# Intercom.net
KiCad netlist of a schematic drawn in EAGLE
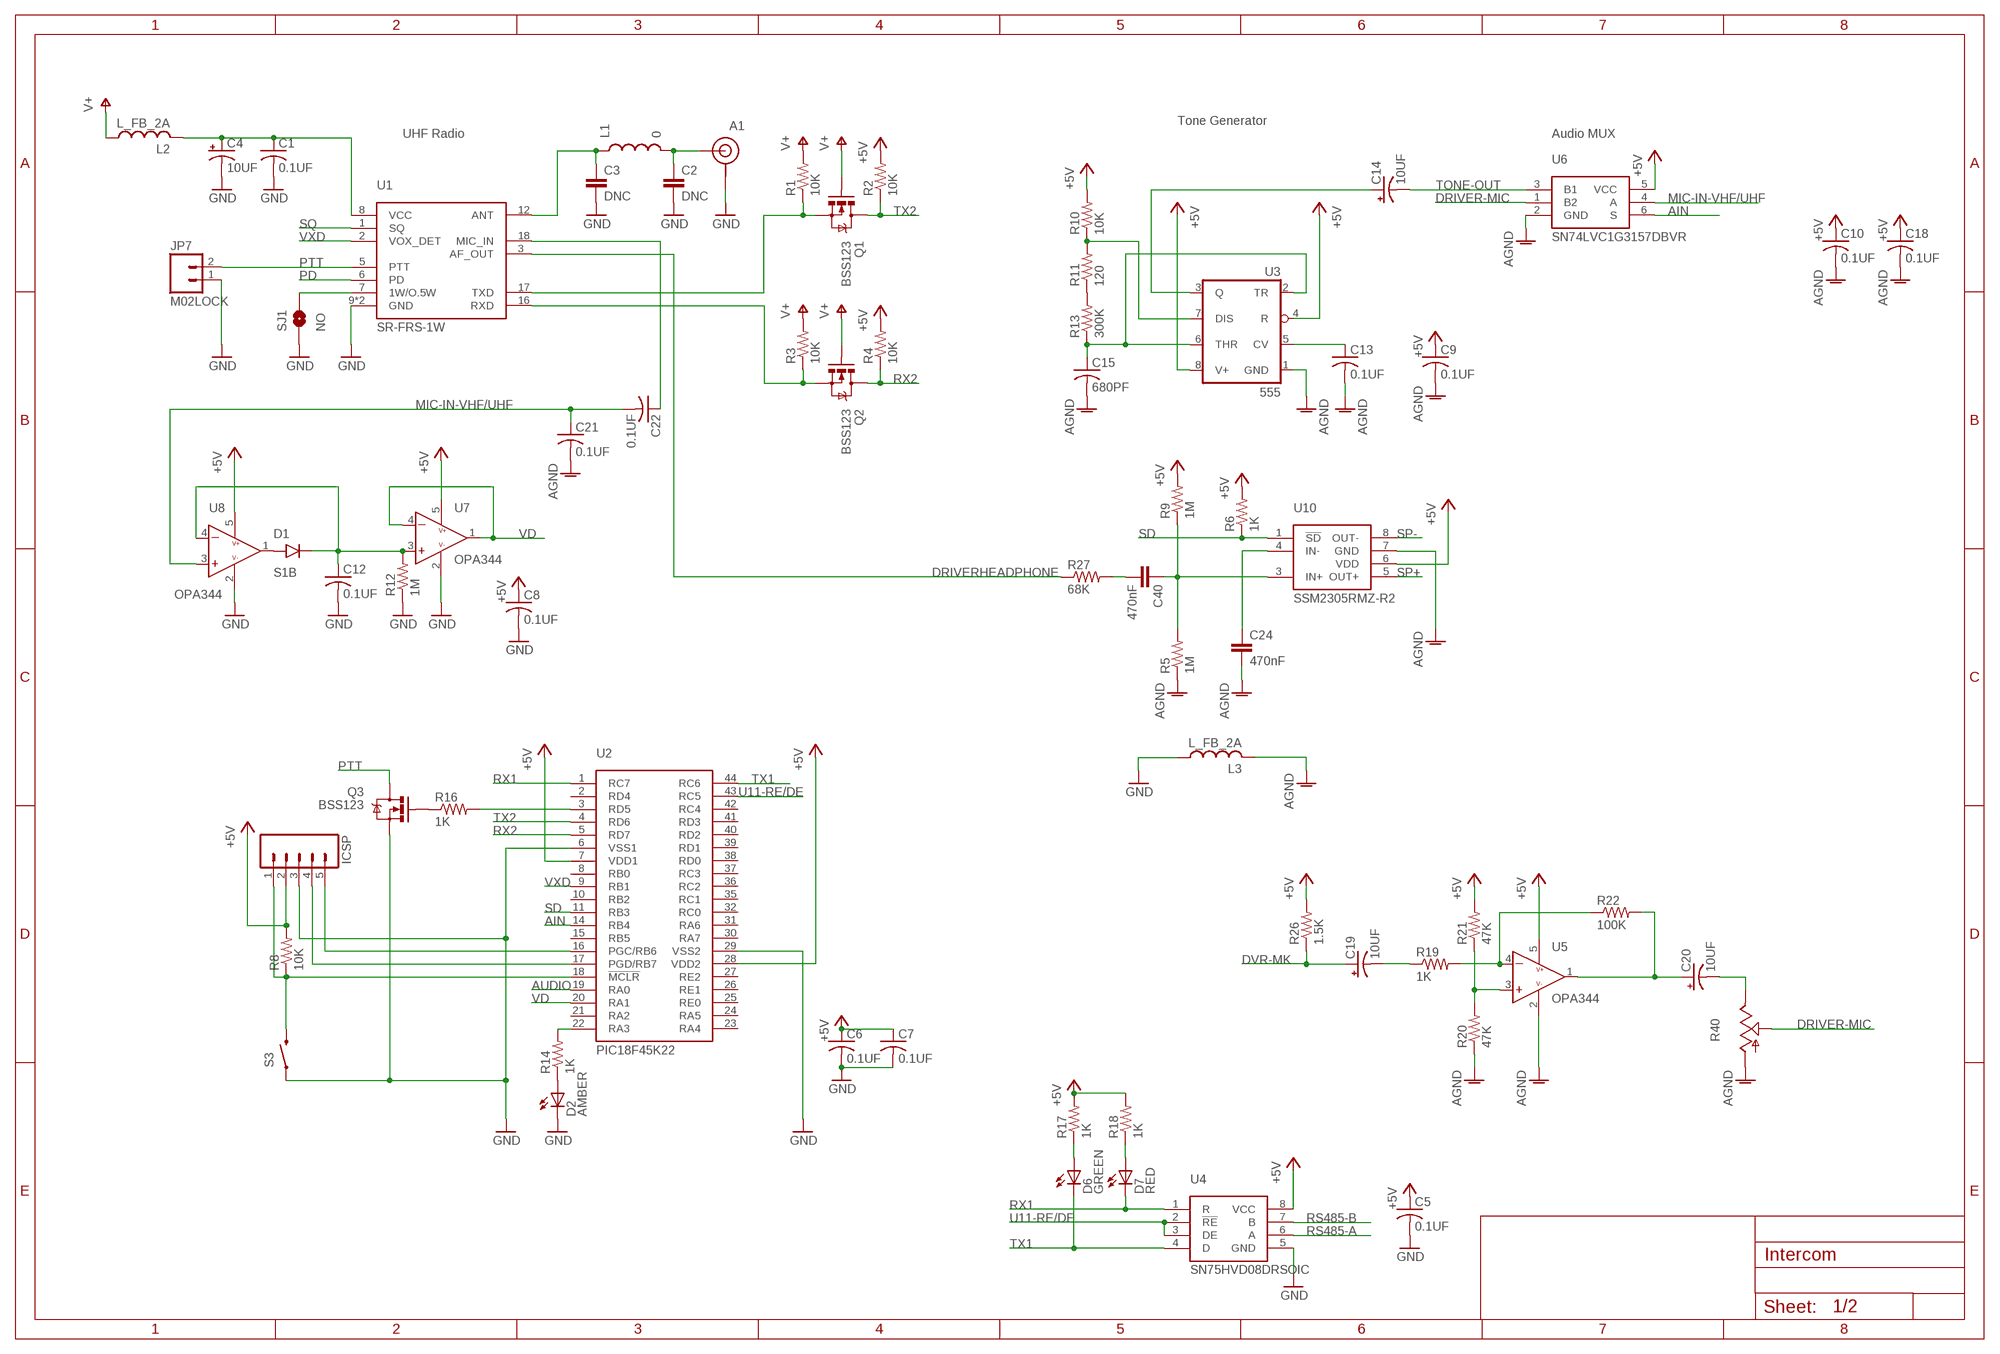
[diagram p0: schematic, sheet 1]
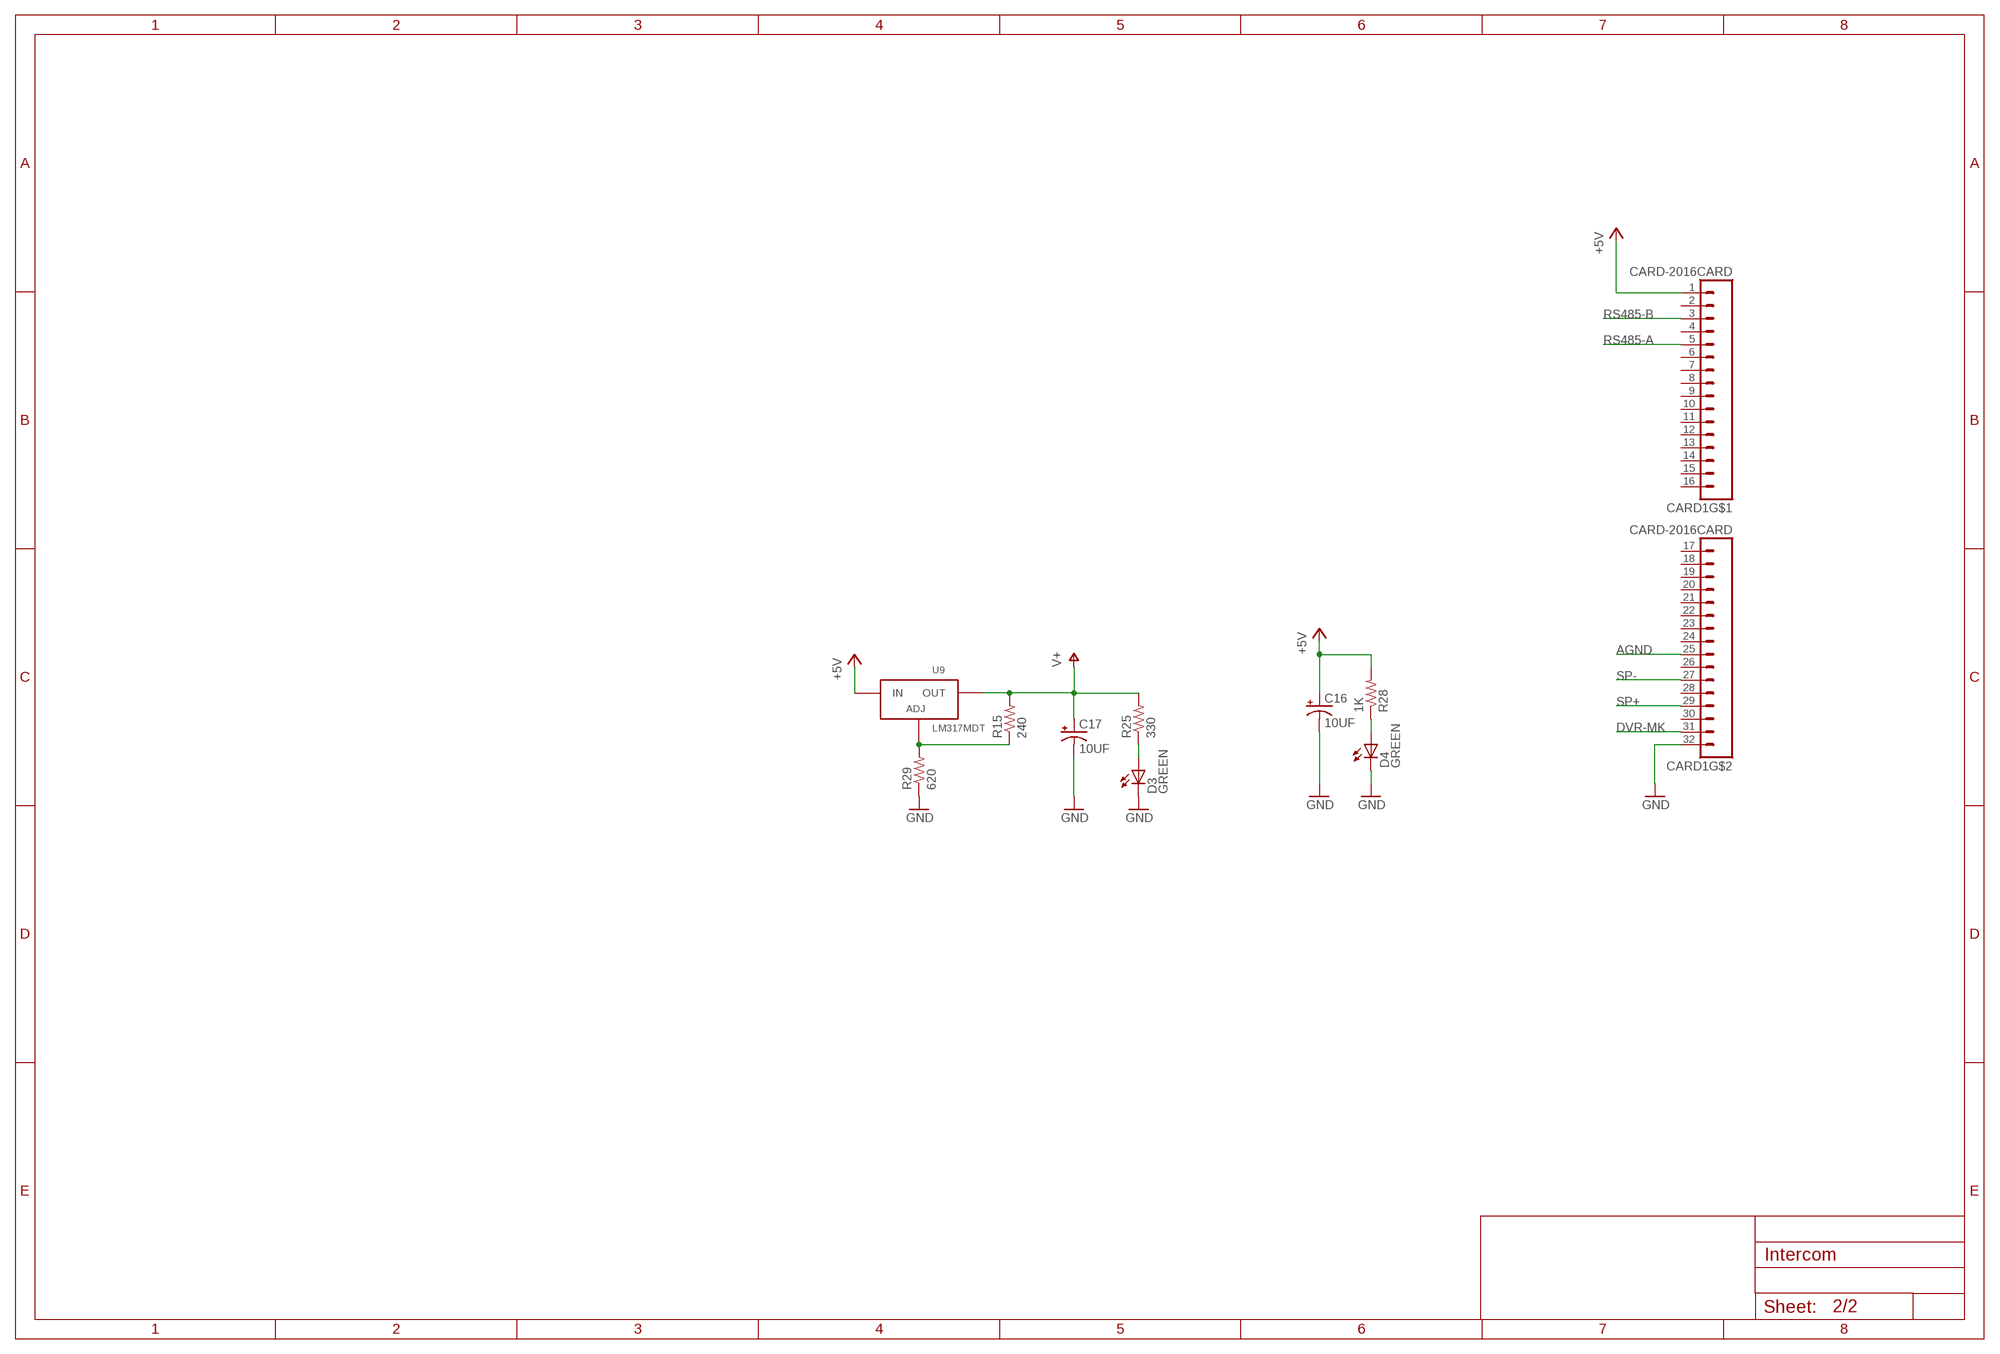
[diagram p1: schematic, sheet 2]

(export (version "E")
  (design (tool "Eeschema 10.0.6"))
  (components
    (comp (ref "A1")
      (value "CONSMA003.062")
      (footprint "eagle-import:CONSMA003.062")
      (fields (field (name "PARTNO") "CONREVSMA003.031"))
      (libsource (lib "eagle-import") (part "CONSMA003.062"))
    )
    (comp (ref "C1")
      (value "0.1UF")
      (footprint "eagle-import:0805")
      (fields (field (name "PARTNO") "CC0805ZRY5V9BB104"))
      (libsource (lib "eagle-import") (part "CAP_0.1UF_50V_0805"))
    )
    (comp (ref "C2")
      (value "DNC")
      (footprint "eagle-import:0805")
      (libsource (lib "eagle-import") (part "CAP0805"))
    )
    (comp (ref "C3")
      (value "DNC")
      (footprint "eagle-import:0805")
      (libsource (lib "eagle-import") (part "CAP0805"))
    )
    (comp (ref "C4")
      (value "10UF")
      (footprint "eagle-import:EIA3216-16V")
      (fields (field (name "PARTNO") "T491A106M016AT"))
      (libsource (lib "eagle-import") (part "CAP-POL_10UF_16V"))
    )
    (comp (ref "C5")
      (value "0.1UF")
      (footprint "eagle-import:0805")
      (fields (field (name "PARTNO") "CC0805ZRY5V9BB104"))
      (libsource (lib "eagle-import") (part "CAP_0.1UF_50V_0805"))
    )
    (comp (ref "C6")
      (value "0.1UF")
      (footprint "eagle-import:0805")
      (fields (field (name "PARTNO") "CC0805ZRY5V9BB104"))
      (libsource (lib "eagle-import") (part "CAP_0.1UF_50V_0805"))
    )
    (comp (ref "C7")
      (value "0.1UF")
      (footprint "eagle-import:0805")
      (fields (field (name "PARTNO") "CC0805ZRY5V9BB104"))
      (libsource (lib "eagle-import") (part "CAP_0.1UF_50V_0805"))
    )
    (comp (ref "C8")
      (value "0.1UF")
      (footprint "eagle-import:0805")
      (fields (field (name "PARTNO") "CC0805ZRY5V9BB104"))
      (libsource (lib "eagle-import") (part "CAP_0.1UF_50V_0805"))
    )
    (comp (ref "C9")
      (value "0.1UF")
      (footprint "eagle-import:0805")
      (fields (field (name "PARTNO") "CC0805ZRY5V9BB104"))
      (libsource (lib "eagle-import") (part "CAP_0.1UF_50V_0805"))
    )
    (comp (ref "C10")
      (value "0.1UF")
      (footprint "eagle-import:0805")
      (fields (field (name "PARTNO") "CC0805ZRY5V9BB104"))
      (libsource (lib "eagle-import") (part "CAP_0.1UF_50V_0805"))
    )
    (comp (ref "C12")
      (value "0.1UF")
      (footprint "eagle-import:0805")
      (fields (field (name "PARTNO") "CC0805ZRY5V9BB104"))
      (libsource (lib "eagle-import") (part "CAP_0.1UF_50V_0805"))
    )
    (comp (ref "C13")
      (value "0.1UF")
      (footprint "eagle-import:0805")
      (fields (field (name "PARTNO") "CC0805ZRY5V9BB104"))
      (libsource (lib "eagle-import") (part "CAP_0.1UF_50V_0805"))
    )
    (comp (ref "C14")
      (value "10UF")
      (footprint "eagle-import:EIA3216-16V")
      (fields (field (name "PARTNO") "T491A106M016AT"))
      (libsource (lib "eagle-import") (part "CAP-POL_10UF_16V"))
    )
    (comp (ref "C15")
      (value "680PF")
      (footprint "eagle-import:0805")
      (fields (field (name "PARTNO") "CC0805KRX7R9BB681"))
      (libsource (lib "eagle-import") (part "CAP_680PF_50V"))
    )
    (comp (ref "C18")
      (value "0.1UF")
      (footprint "eagle-import:0805")
      (fields (field (name "PARTNO") "CC0805ZRY5V9BB104"))
      (libsource (lib "eagle-import") (part "CAP_0.1UF_50V_0805"))
    )
    (comp (ref "C19")
      (value "10UF")
      (footprint "eagle-import:EIA3216-16V")
      (fields (field (name "PARTNO") "T491A106M016AT"))
      (libsource (lib "eagle-import") (part "CAP-POL_10UF_16V"))
    )
    (comp (ref "C20")
      (value "10UF")
      (footprint "eagle-import:EIA3216-16V")
      (fields (field (name "PARTNO") "T491A106M016AT"))
      (libsource (lib "eagle-import") (part "CAP-POL_10UF_16V"))
    )
    (comp (ref "C21")
      (value "0.1UF")
      (footprint "eagle-import:0805")
      (fields (field (name "PARTNO") "CC0805ZRY5V9BB104"))
      (libsource (lib "eagle-import") (part "CAP_0.1UF_50V_0805"))
    )
    (comp (ref "C22")
      (value "0.1UF")
      (footprint "eagle-import:0805")
      (fields (field (name "PARTNO") "CC0805ZRY5V9BB104"))
      (libsource (lib "eagle-import") (part "CAP_0.1UF_50V_0805"))
    )
    (comp (ref "C24")
      (value "470nF")
      (footprint "eagle-import:0805")
      (libsource (lib "eagle-import") (part "CAP0805"))
    )
    (comp (ref "C40")
      (value "470nF")
      (footprint "eagle-import:0805")
      (libsource (lib "eagle-import") (part "CAP0805"))
    )
    (comp (ref "D1")
      (value "S1B")
      (footprint "eagle-import:SMA")
      (libsource (lib "eagle-import") (part "DIODE_S1B"))
    )
    (comp (ref "D2")
      (value "AMBER")
      (footprint "eagle-import:CHIP_LED0805")
      (fields (field (name "PARTNO") "HSMA-C170"))
      (libsource (lib "eagle-import") (part "LED_AMBER"))
    )
    (comp (ref "D6")
      (value "GREEN")
      (footprint "eagle-import:CHIP_LED0805")
      (fields (field (name "PARTNO") "LTST-S220GKT"))
      (libsource (lib "eagle-import") (part "LED_GREEN"))
    )
    (comp (ref "D7")
      (value "RED")
      (footprint "eagle-import:CHIP_LED0805")
      (fields (field (name "PARTNO") "LH R974-LP-1"))
      (libsource (lib "eagle-import") (part "LED_RED"))
    )
    (comp (ref "ICSP")
      (value "M05LOCK_LONGPADS")
      (footprint "eagle-import:1X05_LOCK_LONGPADS")
      (libsource (lib "eagle-import") (part "M05LOCK_LONGPADS"))
    )
    (comp (ref "JP7")
      (value "M02LOCK")
      (footprint "eagle-import:1X02_LOCK")
      (libsource (lib "eagle-import") (part "M02LOCK"))
    )
    (comp (ref "L1")
      (value "0")
      (footprint "eagle-import:1007")
      (libsource (lib "eagle-import") (part "INDUCTOR1007"))
    )
    (comp (ref "L2")
      (value "L_FB_2A")
      (footprint "eagle-import:0805")
      (fields (field (name "PARTNO") "FBMH2012HM121-T"))
      (libsource (lib "eagle-import") (part "L_FB_2A"))
    )
    (comp (ref "L3")
      (value "L_FB_2A")
      (footprint "eagle-import:0805")
      (fields (field (name "PARTNO") "FBMH2012HM121-T"))
      (libsource (lib "eagle-import") (part "L_FB_2A"))
    )
    (comp (ref "Q1")
      (value "BSS123")
      (footprint "eagle-import:SOT23")
      (fields (field (name "PARTNO") "BSS123,215"))
      (libsource (lib "eagle-import") (part "MOS-N_BSS123"))
    )
    (comp (ref "Q2")
      (value "BSS123")
      (footprint "eagle-import:SOT23")
      (fields (field (name "PARTNO") "BSS123,215"))
      (libsource (lib "eagle-import") (part "MOS-N_BSS123"))
    )
    (comp (ref "Q3")
      (value "BSS123")
      (footprint "eagle-import:SOT23")
      (fields (field (name "PARTNO") "BSS123,215"))
      (libsource (lib "eagle-import") (part "MOS-N_BSS123"))
    )
    (comp (ref "R1")
      (value "10K")
      (footprint "eagle-import:0805")
      (fields (field (name "PARTNO") "RC0805FR-0710KL"))
      (libsource (lib "eagle-import") (part "RES_10K_1%_0805"))
    )
    (comp (ref "R2")
      (value "10K")
      (footprint "eagle-import:0805")
      (fields (field (name "PARTNO") "RC0805FR-0710KL"))
      (libsource (lib "eagle-import") (part "RES_10K_1%_0805"))
    )
    (comp (ref "R3")
      (value "10K")
      (footprint "eagle-import:0805")
      (fields (field (name "PARTNO") "RC0805FR-0710KL"))
      (libsource (lib "eagle-import") (part "RES_10K_1%_0805"))
    )
    (comp (ref "R4")
      (value "10K")
      (footprint "eagle-import:0805")
      (fields (field (name "PARTNO") "RC0805FR-0710KL"))
      (libsource (lib "eagle-import") (part "RES_10K_1%_0805"))
    )
    (comp (ref "R5")
      (value "1M")
      (footprint "eagle-import:0805")
      (fields (field (name "PARTNO") "RC0805FR-071ML"))
      (libsource (lib "eagle-import") (part "RES_1M_1%_0805"))
    )
    (comp (ref "R6")
      (value "1K")
      (footprint "eagle-import:0805")
      (fields (field (name "PARTNO") "RC0805FR-071KL"))
      (libsource (lib "eagle-import") (part "RES_1K_1%_0805"))
    )
    (comp (ref "R8")
      (value "10K")
      (footprint "eagle-import:0805")
      (fields (field (name "PARTNO") "RC0805FR-0710KL"))
      (libsource (lib "eagle-import") (part "RES_10K_1%_0805"))
    )
    (comp (ref "R9")
      (value "1M")
      (footprint "eagle-import:0805")
      (fields (field (name "PARTNO") "RC0805FR-071ML"))
      (libsource (lib "eagle-import") (part "RES_1M_1%_0805"))
    )
    (comp (ref "R10")
      (value "10K")
      (footprint "eagle-import:0805")
      (fields (field (name "PARTNO") "RC0805FR-0710KL"))
      (libsource (lib "eagle-import") (part "RES_10K_1%_0805"))
    )
    (comp (ref "R11")
      (value "120")
      (footprint "eagle-import:0805")
      (fields (field (name "PARTNO") "RC0805FR-07120RL"))
      (libsource (lib "eagle-import") (part "RES_120_1%_0805"))
    )
    (comp (ref "R12")
      (value "1M")
      (footprint "eagle-import:0805")
      (fields (field (name "PARTNO") "RC0805FR-071ML"))
      (libsource (lib "eagle-import") (part "RES_1M_1%_0805"))
    )
    (comp (ref "R13")
      (value "300K")
      (footprint "eagle-import:0805")
      (fields (field (name "PARTNO") "RC0805FR-07300KL"))
      (libsource (lib "eagle-import") (part "RES_300K_1%_0805"))
    )
    (comp (ref "R14")
      (value "1K")
      (footprint "eagle-import:0805")
      (fields (field (name "PARTNO") "RC0805FR-071KL"))
      (libsource (lib "eagle-import") (part "RES_1K_1%_0805"))
    )
    (comp (ref "R16")
      (value "1K")
      (footprint "eagle-import:0805")
      (fields (field (name "PARTNO") "RC0805FR-071KL"))
      (libsource (lib "eagle-import") (part "RES_1K_1%_0805"))
    )
    (comp (ref "R17")
      (value "1K")
      (footprint "eagle-import:0805")
      (fields (field (name "PARTNO") "RC0805FR-071KL"))
      (libsource (lib "eagle-import") (part "RES_1K_1%_0805"))
    )
    (comp (ref "R18")
      (value "1K")
      (footprint "eagle-import:0805")
      (fields (field (name "PARTNO") "RC0805FR-071KL"))
      (libsource (lib "eagle-import") (part "RES_1K_1%_0805"))
    )
    (comp (ref "R19")
      (value "1K")
      (footprint "eagle-import:0805")
      (fields (field (name "PARTNO") "RC0805FR-071KL"))
      (libsource (lib "eagle-import") (part "RES_1K_1%_0805"))
    )
    (comp (ref "R20")
      (value "47K")
      (footprint "eagle-import:0805")
      (fields (field (name "PARTNO") "RC0805FR-0747KL"))
      (libsource (lib "eagle-import") (part "RES_47K_1%_0805"))
    )
    (comp (ref "R21")
      (value "47K")
      (footprint "eagle-import:0805")
      (fields (field (name "PARTNO") "RC0805FR-0747KL"))
      (libsource (lib "eagle-import") (part "RES_47K_1%_0805"))
    )
    (comp (ref "R22")
      (value "100K")
      (footprint "eagle-import:0805")
      (fields (field (name "PARTNO") "RC0805FR-07100KL"))
      (libsource (lib "eagle-import") (part "RES_100K_1%_0805"))
    )
    (comp (ref "R26")
      (value "1.5K")
      (footprint "eagle-import:0805")
      (fields (field (name "PARTNO") "RC0805FR-071K5L"))
      (libsource (lib "eagle-import") (part "RES_1.5K_1%_0805"))
    )
    (comp (ref "R27")
      (value "68K")
      (footprint "eagle-import:0805")
      (fields (field (name "PARTNO") "RC0805FR-0768KL"))
      (libsource (lib "eagle-import") (part "RES_68K_1%_0805"))
    )
    (comp (ref "R40")
      (value "TRIM_US-CA6H")
      (footprint "eagle-import:CA6H")
      (libsource (lib "eagle-import") (part "TRIM_US-CA6H"))
    )
    (comp (ref "S3")
      (value "SWITCH-MOMENTARY-2SIDE_EZ")
      (footprint "eagle-import:TACTILE-PTH-SIDEEZ")
      (libsource (lib "eagle-import") (part "SWITCH-MOMENTARY-2SIDE_EZ"))
    )
    (comp (ref "SJ1")
      (value "NO")
      (footprint "eagle-import:SJ_2S-NO")
      (libsource (lib "eagle-import") (part "SOLDERJUMPERNO"))
    )
    (comp (ref "U1")
      (value "SR-FRS-1W")
      (footprint "eagle-import:SR-FRS-1W")
      (libsource (lib "eagle-import") (part "SR-FRS-1W"))
    )
    (comp (ref "U2")
      (value "PIC18F45K22")
      (footprint "eagle-import:TQFP-44")
      (fields (field (name "PARTNO") "PIC18F45K22T-I/PT"))
      (libsource (lib "eagle-import") (part "PIC18F45K22"))
    )
    (comp (ref "U3")
      (value "555")
      (footprint "eagle-import:SO-8")
      (fields (field (name "PARTNO") "NE555PSR"))
      (libsource (lib "eagle-import") (part "555"))
    )
    (comp (ref "U4")
      (value "SN75HVD08DRSOIC")
      (footprint "eagle-import:SO-8")
      (fields (field (name "PARTNO") "SN75HVD08DR"))
      (libsource (lib "eagle-import") (part "SN75HVD08DRSOIC"))
    )
    (comp (ref "U5")
      (value "OPA344")
      (footprint "eagle-import:SOT23-5")
      (fields (field (name "PARTNO") "OPA344NA/3K"))
      (libsource (lib "eagle-import") (part "OPA344"))
    )
    (comp (ref "U6")
      (value "SN74LVC1G3157DBVR")
      (footprint "eagle-import:SOT23-6")
      (libsource (lib "eagle-import") (part "SN74LVC1G3157DBVR"))
    )
    (comp (ref "U7")
      (value "OPA344")
      (footprint "eagle-import:SOT23-5")
      (fields (field (name "PARTNO") "OPA344NA/3K"))
      (libsource (lib "eagle-import") (part "OPA344"))
    )
    (comp (ref "U8")
      (value "OPA344")
      (footprint "eagle-import:SOT23-5")
      (fields (field (name "PARTNO") "OPA344NA/3K"))
      (libsource (lib "eagle-import") (part "OPA344"))
    )
    (comp (ref "U10")
      (value "SSM2305RMZ-R2")
      (footprint "eagle-import:MSOP-8")
      (libsource (lib "eagle-import") (part "SSM2305RMZ-R2"))
    )
    (comp (ref "C16")
      (value "10UF")
      (footprint "eagle-import:EIA3216-16V")
      (fields (field (name "PARTNO") "T491A106M016AT"))
      (libsource (lib "eagle-import") (part "CAP-POL_10UF_16V"))
    )
    (comp (ref "C17")
      (value "10UF")
      (footprint "eagle-import:EIA3216-16V")
      (fields (field (name "PARTNO") "T491A106M016AT"))
      (libsource (lib "eagle-import") (part "CAP-POL_10UF_16V"))
    )
    (comp (ref "CARD1")
      (value "CARD-2016CARD")
      (footprint "eagle-import:CARD-2016")
      (libsource (lib "eagle-import") (part "CARD-2016CARD"))
    )
    (comp (ref "D3")
      (value "GREEN")
      (footprint "eagle-import:CHIP_LED0805")
      (fields (field (name "PARTNO") "LTST-S220GKT"))
      (libsource (lib "eagle-import") (part "LED_GREEN"))
    )
    (comp (ref "D4")
      (value "GREEN")
      (footprint "eagle-import:CHIP_LED0805")
      (fields (field (name "PARTNO") "LTST-S220GKT"))
      (libsource (lib "eagle-import") (part "LED_GREEN"))
    )
    (comp (ref "R15")
      (value "240")
      (footprint "eagle-import:0805")
      (fields (field (name "PARTNO") "RMCF0805FT240R"))
      (libsource (lib "eagle-import") (part "RES_240_1%_0805"))
    )
    (comp (ref "R25")
      (value "330")
      (footprint "eagle-import:0805")
      (fields (field (name "PARTNO") "RC0805FR-07330RL"))
      (libsource (lib "eagle-import") (part "RES_330_1%_0805"))
    )
    (comp (ref "R28")
      (value "1K")
      (footprint "eagle-import:0805")
      (fields (field (name "PARTNO") "RC0805FR-071KL"))
      (libsource (lib "eagle-import") (part "RES_1K_1%_0805"))
    )
    (comp (ref "R29")
      (value "620")
      (footprint "eagle-import:0805")
      (fields (field (name "PARTNO") "RC0805FR-07620RL"))
      (libsource (lib "eagle-import") (part "RES_620_1%_0805"))
    )
    (comp (ref "U9")
      (value "LM317MDT")
      (footprint "eagle-import:DPAK")
      (fields (field (name "PARTNO") "LM317MDT-TR"))
      (libsource (lib "eagle-import") (part "LM317MDT"))
    )
  )
  (nets
    (net (code "1") (name "+5V") (class "Default")
      (node (ref "C10") (pin "1") (pinfunction "+_1") (pintype "passive"))
      (node (ref "C16") (pin "A") (pinfunction "+_A") (pintype "passive"))
      (node (ref "C18") (pin "1") (pinfunction "+_1") (pintype "passive"))
      (node (ref "C5") (pin "1") (pinfunction "+_1") (pintype "passive"))
      (node (ref "C6") (pin "1") (pinfunction "+_1") (pintype "passive"))
      (node (ref "C7") (pin "1") (pinfunction "+_1") (pintype "passive"))
      (node (ref "C8") (pin "1") (pinfunction "+_1") (pintype "passive"))
      (node (ref "C9") (pin "1") (pinfunction "+_1") (pintype "passive"))
      (node (ref "CARD1") (pin "1") (pinfunction "1_1") (pintype "passive"))
      (node (ref "ICSP") (pin "2") (pinfunction "2_2") (pintype "passive"))
      (node (ref "R10") (pin "2") (pinfunction "2_2") (pintype "passive"))
      (node (ref "R17") (pin "2") (pinfunction "2_2") (pintype "passive"))
      (node (ref "R18") (pin "2") (pinfunction "2_2") (pintype "passive"))
      (node (ref "R2") (pin "2") (pinfunction "2_2") (pintype "passive"))
      (node (ref "R21") (pin "2") (pinfunction "2_2") (pintype "passive"))
      (node (ref "R26") (pin "2") (pinfunction "2_2") (pintype "passive"))
      (node (ref "R28") (pin "2") (pinfunction "2_2") (pintype "passive"))
      (node (ref "R4") (pin "2") (pinfunction "2_2") (pintype "passive"))
      (node (ref "R6") (pin "2") (pinfunction "2_2") (pintype "passive"))
      (node (ref "R8") (pin "2") (pinfunction "2_2") (pintype "passive"))
      (node (ref "R9") (pin "2") (pinfunction "2_2") (pintype "passive"))
      (node (ref "U10") (pin "6") (pinfunction "VDD_6") (pintype "bidirectional"))
      (node (ref "U2") (pin "28") (pinfunction "VDD2_28") (pintype "bidirectional"))
      (node (ref "U2") (pin "7") (pinfunction "VDD1_7") (pintype "bidirectional"))
      (node (ref "U3") (pin "4") (pinfunction "R_4") (pintype "input"))
      (node (ref "U3") (pin "8") (pinfunction "V+_8") (pintype "power_in"))
      (node (ref "U4") (pin "8") (pinfunction "VCC_8") (pintype "bidirectional"))
      (node (ref "U5") (pin "5") (pinfunction "V+_5") (pintype "bidirectional"))
      (node (ref "U6") (pin "5") (pinfunction "VCC_5") (pintype "bidirectional"))
      (node (ref "U7") (pin "5") (pinfunction "V+_5") (pintype "bidirectional"))
      (node (ref "U8") (pin "5") (pinfunction "V+_5") (pintype "bidirectional"))
      (node (ref "U9") (pin "2") (pinfunction "IN_2") (pintype "bidirectional"))
    )
    (net (code "2") (name "AGND") (class "Default")
      (node (ref "C10") (pin "2") (pinfunction "-_2") (pintype "passive"))
      (node (ref "C13") (pin "2") (pinfunction "-_2") (pintype "passive"))
      (node (ref "C15") (pin "2") (pinfunction "-_2") (pintype "passive"))
      (node (ref "C18") (pin "2") (pinfunction "-_2") (pintype "passive"))
      (node (ref "C21") (pin "2") (pinfunction "-_2") (pintype "passive"))
      (node (ref "C24") (pin "2") (pinfunction "2_2") (pintype "passive"))
      (node (ref "C9") (pin "2") (pinfunction "-_2") (pintype "passive"))
      (node (ref "CARD1") (pin "25") (pinfunction "9_25") (pintype "passive"))
      (node (ref "L3") (pin "2") (pinfunction "2_2") (pintype "passive"))
      (node (ref "R20") (pin "1") (pinfunction "1_1") (pintype "passive"))
      (node (ref "R40") (pin "A") (pinfunction "A_A") (pintype "passive"))
      (node (ref "R5") (pin "1") (pinfunction "1_1") (pintype "passive"))
      (node (ref "U10") (pin "7") (pinfunction "GND_7") (pintype "bidirectional"))
      (node (ref "U3") (pin "1") (pinfunction "GND_1") (pintype "power_in"))
      (node (ref "U5") (pin "2") (pinfunction "V-_2") (pintype "bidirectional"))
      (node (ref "U6") (pin "2") (pinfunction "GND_2") (pintype "bidirectional"))
    )
    (net (code "3") (name "AIN") (class "Default")
      (node (ref "U2") (pin "14") (pinfunction "RB4_14") (pintype "bidirectional"))
      (node (ref "U6") (pin "6") (pinfunction "S_6") (pintype "bidirectional"))
    )
    (net (code "4") (name "AUDIO") (class "Default")
      (node (ref "U2") (pin "19") (pinfunction "RA0_19") (pintype "bidirectional"))
    )
    (net (code "5") (name "DRIVER-MIC") (class "Default")
      (node (ref "R40") (pin "S") (pinfunction "S_S") (pintype "passive"))
      (node (ref "U6") (pin "1") (pinfunction "B2_1") (pintype "bidirectional"))
    )
    (net (code "6") (name "DRIVERHEADPHONE") (class "Default")
      (node (ref "R27") (pin "1") (pinfunction "1_1") (pintype "passive"))
      (node (ref "U1") (pin "3") (pinfunction "AF_OUT_3") (pintype "bidirectional"))
    )
    (net (code "7") (name "DVR-MK") (class "Default")
      (node (ref "C19") (pin "A") (pinfunction "+_A") (pintype "passive"))
      (node (ref "CARD1") (pin "31") (pinfunction "15_31") (pintype "passive"))
      (node (ref "R26") (pin "1") (pinfunction "1_1") (pintype "passive"))
    )
    (net (code "8") (name "GND") (class "Default")
      (node (ref "A1") (pin "G") (pinfunction "GND_G") (pintype "bidirectional"))
      (node (ref "A1") (pin "G1") (pinfunction "GND_G1") (pintype "bidirectional"))
      (node (ref "A1") (pin "G2") (pinfunction "GND_G2") (pintype "bidirectional"))
      (node (ref "A1") (pin "G3") (pinfunction "GND_G3") (pintype "bidirectional"))
      (node (ref "C1") (pin "2") (pinfunction "-_2") (pintype "passive"))
      (node (ref "C12") (pin "2") (pinfunction "-_2") (pintype "passive"))
      (node (ref "C16") (pin "C") (pinfunction "-_C") (pintype "passive"))
      (node (ref "C17") (pin "C") (pinfunction "-_C") (pintype "passive"))
      (node (ref "C2") (pin "2") (pinfunction "2_2") (pintype "passive"))
      (node (ref "C3") (pin "2") (pinfunction "2_2") (pintype "passive"))
      (node (ref "C4") (pin "C") (pinfunction "-_C") (pintype "passive"))
      (node (ref "C5") (pin "2") (pinfunction "-_2") (pintype "passive"))
      (node (ref "C6") (pin "2") (pinfunction "-_2") (pintype "passive"))
      (node (ref "C7") (pin "2") (pinfunction "-_2") (pintype "passive"))
      (node (ref "C8") (pin "2") (pinfunction "-_2") (pintype "passive"))
      (node (ref "CARD1") (pin "32") (pinfunction "16_32") (pintype "passive"))
      (node (ref "D2") (pin "C") (pinfunction "C_C") (pintype "passive"))
      (node (ref "D3") (pin "C") (pinfunction "C_C") (pintype "passive"))
      (node (ref "D4") (pin "C") (pinfunction "C_C") (pintype "passive"))
      (node (ref "ICSP") (pin "3") (pinfunction "3_3") (pintype "passive"))
      (node (ref "JP7") (pin "1") (pinfunction "1_1") (pintype "passive"))
      (node (ref "L3") (pin "1") (pinfunction "1_1") (pintype "passive"))
      (node (ref "Q3") (pin "2") (pinfunction "S_2") (pintype "passive"))
      (node (ref "R12") (pin "1") (pinfunction "1_1") (pintype "passive"))
      (node (ref "R29") (pin "1") (pinfunction "1_1") (pintype "passive"))
      (node (ref "S3") (pin "1") (pinfunction "1_1") (pintype "passive"))
      (node (ref "SJ1") (pin "1") (pinfunction "1_1") (pintype "passive"))
      (node (ref "U1") (pin "10") (pinfunction "GND_10") (pintype "bidirectional"))
      (node (ref "U1") (pin "9") (pinfunction "GND_9") (pintype "bidirectional"))
      (node (ref "U2") (pin "29") (pinfunction "VSS2_29") (pintype "bidirectional"))
      (node (ref "U2") (pin "6") (pinfunction "VSS1_6") (pintype "bidirectional"))
      (node (ref "U4") (pin "5") (pinfunction "GND_5") (pintype "bidirectional"))
      (node (ref "U7") (pin "2") (pinfunction "V-_2") (pintype "bidirectional"))
      (node (ref "U8") (pin "2") (pinfunction "V-_2") (pintype "bidirectional"))
    )
    (net (code "9") (name "MIC-IN-VHF{slash}UHF") (class "Default")
      (node (ref "C21") (pin "1") (pinfunction "+_1") (pintype "passive"))
      (node (ref "C22") (pin "2") (pinfunction "-_2") (pintype "passive"))
      (node (ref "U6") (pin "4") (pinfunction "A_4") (pintype "bidirectional"))
      (node (ref "U8") (pin "3") (pinfunction "+_3") (pintype "bidirectional"))
    )
    (net (code "10") (name "Net-(A1-SIGNAL)") (class "Default")
      (node (ref "A1") (pin "S") (pinfunction "SIGNAL_S") (pintype "bidirectional"))
      (node (ref "C2") (pin "1") (pinfunction "1_1") (pintype "passive"))
      (node (ref "L1") (pin "2") (pinfunction "2_2") (pintype "passive"))
    )
    (net (code "11") (name "Net-(C1-+)") (class "Default")
      (node (ref "C1") (pin "1") (pinfunction "+_1") (pintype "passive"))
      (node (ref "C4") (pin "A") (pinfunction "+_A") (pintype "passive"))
      (node (ref "L2") (pin "2") (pinfunction "2_2") (pintype "passive"))
      (node (ref "U1") (pin "8") (pinfunction "VCC_8") (pintype "bidirectional"))
    )
    (net (code "12") (name "Net-(C12-+)") (class "Default")
      (node (ref "C12") (pin "1") (pinfunction "+_1") (pintype "passive"))
      (node (ref "D1") (pin "C") (pinfunction "C_C") (pintype "bidirectional"))
      (node (ref "R12") (pin "2") (pinfunction "2_2") (pintype "passive"))
      (node (ref "U7") (pin "3") (pinfunction "+_3") (pintype "bidirectional"))
      (node (ref "U8") (pin "4") (pinfunction "-_4") (pintype "bidirectional"))
    )
    (net (code "13") (name "Net-(C13-+)") (class "Default")
      (node (ref "C13") (pin "1") (pinfunction "+_1") (pintype "passive"))
      (node (ref "U3") (pin "5") (pinfunction "CV_5") (pintype "input"))
    )
    (net (code "14") (name "Net-(C14-+)") (class "Default")
      (node (ref "C14") (pin "A") (pinfunction "+_A") (pintype "passive"))
      (node (ref "U3") (pin "3") (pinfunction "Q_3") (pintype "output"))
    )
    (net (code "15") (name "Net-(C15-+)") (class "Default")
      (node (ref "C15") (pin "1") (pinfunction "+_1") (pintype "passive"))
      (node (ref "R13") (pin "1") (pinfunction "1_1") (pintype "passive"))
      (node (ref "U3") (pin "2") (pinfunction "TR_2") (pintype "input"))
      (node (ref "U3") (pin "6") (pinfunction "THR_6") (pintype "input"))
    )
    (net (code "16") (name "Net-(C19--)") (class "Default")
      (node (ref "C19") (pin "C") (pinfunction "-_C") (pintype "passive"))
      (node (ref "R19") (pin "1") (pinfunction "1_1") (pintype "passive"))
    )
    (net (code "17") (name "Net-(C20-+)") (class "Default")
      (node (ref "C20") (pin "A") (pinfunction "+_A") (pintype "passive"))
      (node (ref "R22") (pin "2") (pinfunction "2_2") (pintype "passive"))
      (node (ref "U5") (pin "1") (pinfunction "O_1") (pintype "bidirectional"))
    )
    (net (code "18") (name "Net-(C20--)") (class "Default")
      (node (ref "C20") (pin "C") (pinfunction "-_C") (pintype "passive"))
      (node (ref "R40") (pin "E") (pinfunction "E_E") (pintype "passive"))
    )
    (net (code "19") (name "Net-(C22-+)") (class "Default")
      (node (ref "C22") (pin "1") (pinfunction "+_1") (pintype "passive"))
      (node (ref "U1") (pin "18") (pinfunction "MIC_IN_18") (pintype "bidirectional"))
    )
    (net (code "20") (name "Net-(C40-Pad2)") (class "Default")
      (node (ref "C40") (pin "2") (pinfunction "2_2") (pintype "passive"))
      (node (ref "R27") (pin "2") (pinfunction "2_2") (pintype "passive"))
    )
    (net (code "21") (name "Net-(D2-PadA)") (class "Default")
      (node (ref "D2") (pin "A") (pinfunction "A_A") (pintype "passive"))
      (node (ref "R14") (pin "1") (pinfunction "1_1") (pintype "passive"))
    )
    (net (code "22") (name "Net-(D3-PadA)") (class "Default")
      (node (ref "D3") (pin "A") (pinfunction "A_A") (pintype "passive"))
      (node (ref "R25") (pin "1") (pinfunction "1_1") (pintype "passive"))
    )
    (net (code "23") (name "Net-(D4-PadA)") (class "Default")
      (node (ref "D4") (pin "A") (pinfunction "A_A") (pintype "passive"))
      (node (ref "R28") (pin "1") (pinfunction "1_1") (pintype "passive"))
    )
    (net (code "24") (name "Net-(D6-PadA)") (class "Default")
      (node (ref "D6") (pin "A") (pinfunction "A_A") (pintype "passive"))
      (node (ref "R17") (pin "1") (pinfunction "1_1") (pintype "passive"))
    )
    (net (code "25") (name "Net-(D7-PadA)") (class "Default")
      (node (ref "D7") (pin "A") (pinfunction "A_A") (pintype "passive"))
      (node (ref "R18") (pin "1") (pinfunction "1_1") (pintype "passive"))
    )
    (net (code "26") (name "Net-(Q1-S)") (class "Default")
      (node (ref "Q1") (pin "2") (pinfunction "S_2") (pintype "passive"))
      (node (ref "R1") (pin "1") (pinfunction "1_1") (pintype "passive"))
      (node (ref "U1") (pin "17") (pinfunction "TXD_17") (pintype "bidirectional"))
    )
    (net (code "27") (name "Net-(Q2-S)") (class "Default")
      (node (ref "Q2") (pin "2") (pinfunction "S_2") (pintype "passive"))
      (node (ref "R3") (pin "1") (pinfunction "1_1") (pintype "passive"))
      (node (ref "U1") (pin "16") (pinfunction "RXD_16") (pintype "bidirectional"))
    )
    (net (code "28") (name "Net-(Q3-G)") (class "Default")
      (node (ref "Q3") (pin "1") (pinfunction "G_1") (pintype "passive"))
      (node (ref "R16") (pin "1") (pinfunction "1_1") (pintype "passive"))
    )
    (net (code "29") (name "Net-(R11-Pad1)") (class "Default")
      (node (ref "R11") (pin "1") (pinfunction "1_1") (pintype "passive"))
      (node (ref "R13") (pin "2") (pinfunction "2_2") (pintype "passive"))
    )
    (net (code "30") (name "Net-(U1-1W{slash}O.5W)") (class "Default")
      (node (ref "SJ1") (pin "2") (pinfunction "2_2") (pintype "passive"))
      (node (ref "U1") (pin "7") (pinfunction "1W/O.5W_7") (pintype "bidirectional"))
    )
    (net (code "31") (name "Net-(U1-ANT)") (class "Default")
      (node (ref "C3") (pin "1") (pinfunction "1_1") (pintype "passive"))
      (node (ref "L1") (pin "1") (pinfunction "1_1") (pintype "passive"))
      (node (ref "U1") (pin "12") (pinfunction "ANT_12") (pintype "bidirectional"))
    )
    (net (code "32") (name "Net-(U2-PGC{slash}RB6)") (class "Default")
      (node (ref "ICSP") (pin "5") (pinfunction "5_5") (pintype "passive"))
      (node (ref "U2") (pin "16") (pinfunction "PGC/RB6_16") (pintype "bidirectional"))
    )
    (net (code "33") (name "Net-(U2-PGD{slash}RB7)") (class "Default")
      (node (ref "ICSP") (pin "4") (pinfunction "4_4") (pintype "passive"))
      (node (ref "U2") (pin "17") (pinfunction "PGD/RB7_17") (pintype "bidirectional"))
    )
    (net (code "34") (name "Net-(U2-RA3)") (class "Default")
      (node (ref "R14") (pin "2") (pinfunction "2_2") (pintype "passive"))
      (node (ref "U2") (pin "22") (pinfunction "RA3_22") (pintype "bidirectional"))
    )
    (net (code "35") (name "Net-(U2-RD5)") (class "Default")
      (node (ref "R16") (pin "2") (pinfunction "2_2") (pintype "passive"))
      (node (ref "U2") (pin "3") (pinfunction "RD5_3") (pintype "bidirectional"))
    )
    (net (code "36") (name "Net-(U2-~{MCLR})") (class "Default")
      (node (ref "ICSP") (pin "1") (pinfunction "1_1") (pintype "passive"))
      (node (ref "R8") (pin "1") (pinfunction "1_1") (pintype "passive"))
      (node (ref "S3") (pin "2") (pinfunction "2_2") (pintype "passive"))
      (node (ref "U2") (pin "18") (pinfunction "~{MCLR}_18") (pintype "bidirectional"))
    )
    (net (code "37") (name "Net-(U3-DIS)") (class "Default")
      (node (ref "R10") (pin "1") (pinfunction "1_1") (pintype "passive"))
      (node (ref "R11") (pin "2") (pinfunction "2_2") (pintype "passive"))
      (node (ref "U3") (pin "7") (pinfunction "DIS_7") (pintype "input"))
    )
    (net (code "38") (name "Net-(U5-+)") (class "Default")
      (node (ref "R20") (pin "2") (pinfunction "2_2") (pintype "passive"))
      (node (ref "R21") (pin "1") (pinfunction "1_1") (pintype "passive"))
      (node (ref "U5") (pin "3") (pinfunction "+_3") (pintype "bidirectional"))
    )
    (net (code "39") (name "Net-(U5--)") (class "Default")
      (node (ref "R19") (pin "2") (pinfunction "2_2") (pintype "passive"))
      (node (ref "R22") (pin "1") (pinfunction "1_1") (pintype "passive"))
      (node (ref "U5") (pin "4") (pinfunction "-_4") (pintype "bidirectional"))
    )
    (net (code "40") (name "Net-(U8-O)") (class "Default")
      (node (ref "D1") (pin "A") (pinfunction "A_A") (pintype "bidirectional"))
      (node (ref "U8") (pin "1") (pinfunction "O_1") (pintype "bidirectional"))
    )
    (net (code "41") (name "Net-(U9-ADJ)") (class "Default")
      (node (ref "R15") (pin "1") (pinfunction "1_1") (pintype "passive"))
      (node (ref "R29") (pin "2") (pinfunction "2_2") (pintype "passive"))
      (node (ref "U9") (pin "1") (pinfunction "ADJ_1") (pintype "bidirectional"))
    )
    (net (code "42") (name "Net-(U10-IN+)") (class "Default")
      (node (ref "C40") (pin "1") (pinfunction "1_1") (pintype "passive"))
      (node (ref "R5") (pin "2") (pinfunction "2_2") (pintype "passive"))
      (node (ref "R9") (pin "1") (pinfunction "1_1") (pintype "passive"))
      (node (ref "U10") (pin "3") (pinfunction "IN+_3") (pintype "bidirectional"))
    )
    (net (code "43") (name "Net-(U10-IN-)") (class "Default")
      (node (ref "C24") (pin "1") (pinfunction "1_1") (pintype "passive"))
      (node (ref "U10") (pin "4") (pinfunction "IN-_4") (pintype "bidirectional"))
    )
    (net (code "44") (name "PD") (class "Default")
      (node (ref "U1") (pin "6") (pinfunction "PD_6") (pintype "bidirectional"))
    )
    (net (code "45") (name "PTT") (class "Default")
      (node (ref "JP7") (pin "2") (pinfunction "2_2") (pintype "passive"))
      (node (ref "Q3") (pin "3") (pinfunction "D_3") (pintype "passive"))
      (node (ref "U1") (pin "5") (pinfunction "PTT_5") (pintype "bidirectional"))
    )
    (net (code "46") (name "RS485-A") (class "Default")
      (node (ref "CARD1") (pin "5") (pinfunction "5_5") (pintype "passive"))
      (node (ref "U4") (pin "6") (pinfunction "A_6") (pintype "bidirectional"))
    )
    (net (code "47") (name "RS485-B") (class "Default")
      (node (ref "CARD1") (pin "3") (pinfunction "3_3") (pintype "passive"))
      (node (ref "U4") (pin "7") (pinfunction "B_7") (pintype "bidirectional"))
    )
    (net (code "48") (name "RX1") (class "Default")
      (node (ref "D7") (pin "C") (pinfunction "C_C") (pintype "passive"))
      (node (ref "U2") (pin "1") (pinfunction "RC7_1") (pintype "bidirectional"))
      (node (ref "U4") (pin "1") (pinfunction "R_1") (pintype "bidirectional"))
    )
    (net (code "49") (name "RX2") (class "Default")
      (node (ref "Q2") (pin "3") (pinfunction "D_3") (pintype "passive"))
      (node (ref "R4") (pin "1") (pinfunction "1_1") (pintype "passive"))
      (node (ref "U2") (pin "5") (pinfunction "RD7_5") (pintype "bidirectional"))
    )
    (net (code "50") (name "SD") (class "Default")
      (node (ref "R6") (pin "1") (pinfunction "1_1") (pintype "passive"))
      (node (ref "U10") (pin "1") (pinfunction "~{SD}_1") (pintype "bidirectional"))
      (node (ref "U2") (pin "11") (pinfunction "RB3_11") (pintype "bidirectional"))
    )
    (net (code "51") (name "SP+") (class "Default")
      (node (ref "CARD1") (pin "29") (pinfunction "13_29") (pintype "passive"))
      (node (ref "U10") (pin "5") (pinfunction "OUT+_5") (pintype "bidirectional"))
    )
    (net (code "52") (name "SP-") (class "Default")
      (node (ref "CARD1") (pin "27") (pinfunction "11_27") (pintype "passive"))
      (node (ref "U10") (pin "8") (pinfunction "OUT-_8") (pintype "bidirectional"))
    )
    (net (code "53") (name "SQ") (class "Default")
      (node (ref "U1") (pin "1") (pinfunction "SQ_1") (pintype "bidirectional"))
    )
    (net (code "54") (name "TONE-OUT") (class "Default")
      (node (ref "C14") (pin "C") (pinfunction "-_C") (pintype "passive"))
      (node (ref "U6") (pin "3") (pinfunction "B1_3") (pintype "bidirectional"))
    )
    (net (code "55") (name "TX1") (class "Default")
      (node (ref "D6") (pin "C") (pinfunction "C_C") (pintype "passive"))
      (node (ref "U2") (pin "44") (pinfunction "RC6_44") (pintype "bidirectional"))
      (node (ref "U4") (pin "4") (pinfunction "D_4") (pintype "bidirectional"))
    )
    (net (code "56") (name "TX2") (class "Default")
      (node (ref "Q1") (pin "3") (pinfunction "D_3") (pintype "passive"))
      (node (ref "R2") (pin "1") (pinfunction "1_1") (pintype "passive"))
      (node (ref "U2") (pin "4") (pinfunction "RD6_4") (pintype "bidirectional"))
    )
    (net (code "57") (name "U11-RE{slash}DE") (class "Default")
      (node (ref "U2") (pin "43") (pinfunction "RC5_43") (pintype "bidirectional"))
      (node (ref "U4") (pin "2") (pinfunction "~{RE}_2") (pintype "bidirectional"))
      (node (ref "U4") (pin "3") (pinfunction "DE_3") (pintype "bidirectional"))
    )
    (net (code "58") (name "V+") (class "Default")
      (node (ref "C17") (pin "A") (pinfunction "+_A") (pintype "passive"))
      (node (ref "L2") (pin "1") (pinfunction "1_1") (pintype "passive"))
      (node (ref "Q1") (pin "1") (pinfunction "G_1") (pintype "passive"))
      (node (ref "Q2") (pin "1") (pinfunction "G_1") (pintype "passive"))
      (node (ref "R1") (pin "2") (pinfunction "2_2") (pintype "passive"))
      (node (ref "R15") (pin "2") (pinfunction "2_2") (pintype "passive"))
      (node (ref "R25") (pin "2") (pinfunction "2_2") (pintype "passive"))
      (node (ref "R3") (pin "2") (pinfunction "2_2") (pintype "passive"))
      (node (ref "U9") (pin "3") (pinfunction "OUT_3") (pintype "bidirectional"))
    )
    (net (code "59") (name "VD") (class "Default")
      (node (ref "U2") (pin "20") (pinfunction "RA1_20") (pintype "bidirectional"))
      (node (ref "U7") (pin "1") (pinfunction "O_1") (pintype "bidirectional"))
      (node (ref "U7") (pin "4") (pinfunction "-_4") (pintype "bidirectional"))
    )
    (net (code "60") (name "VXD") (class "Default")
      (node (ref "U1") (pin "2") (pinfunction "VOX_DET_2") (pintype "bidirectional"))
      (node (ref "U2") (pin "9") (pinfunction "RB1_9") (pintype "bidirectional"))
    )
    (net (code "61") (name "unconnected-(CARD1-Pad2)") (class "Default")
      (node (ref "CARD1") (pin "2") (pinfunction "2_2") (pintype "passive"))
    )
    (net (code "62") (name "unconnected-(CARD1-Pad4)") (class "Default")
      (node (ref "CARD1") (pin "4") (pinfunction "4_4") (pintype "passive"))
    )
    (net (code "63") (name "unconnected-(CARD1-Pad6)") (class "Default")
      (node (ref "CARD1") (pin "6") (pinfunction "6_6") (pintype "passive"))
    )
    (net (code "64") (name "unconnected-(CARD1-Pad7)") (class "Default")
      (node (ref "CARD1") (pin "7") (pinfunction "7_7") (pintype "passive"))
    )
    (net (code "65") (name "unconnected-(CARD1-Pad8)") (class "Default")
      (node (ref "CARD1") (pin "8") (pinfunction "8_8") (pintype "passive"))
    )
    (net (code "66") (name "unconnected-(CARD1-Pad9)") (class "Default")
      (node (ref "CARD1") (pin "9") (pinfunction "9_9") (pintype "passive"))
    )
    (net (code "67") (name "unconnected-(CARD1-Pad10)") (class "Default")
      (node (ref "CARD1") (pin "10") (pinfunction "10_10") (pintype "passive"))
    )
    (net (code "68") (name "unconnected-(CARD1-Pad11)") (class "Default")
      (node (ref "CARD1") (pin "11") (pinfunction "11_11") (pintype "passive"))
    )
    (net (code "69") (name "unconnected-(CARD1-Pad12)") (class "Default")
      (node (ref "CARD1") (pin "12") (pinfunction "12_12") (pintype "passive"))
    )
    (net (code "70") (name "unconnected-(CARD1-Pad13)") (class "Default")
      (node (ref "CARD1") (pin "13") (pinfunction "13_13") (pintype "passive"))
    )
    (net (code "71") (name "unconnected-(CARD1-Pad14)") (class "Default")
      (node (ref "CARD1") (pin "14") (pinfunction "14_14") (pintype "passive"))
    )
    (net (code "72") (name "unconnected-(CARD1-Pad15)") (class "Default")
      (node (ref "CARD1") (pin "15") (pinfunction "15_15") (pintype "passive"))
    )
    (net (code "73") (name "unconnected-(CARD1-Pad16)") (class "Default")
      (node (ref "CARD1") (pin "16") (pinfunction "16_16") (pintype "passive"))
    )
    (net (code "74") (name "unconnected-(CARD1B-1-Pad17)") (class "Default")
      (node (ref "CARD1") (pin "17") (pinfunction "1_17") (pintype "passive"))
    )
    (net (code "75") (name "unconnected-(CARD1B-2-Pad18)") (class "Default")
      (node (ref "CARD1") (pin "18") (pinfunction "2_18") (pintype "passive"))
    )
    (net (code "76") (name "unconnected-(CARD1B-3-Pad19)") (class "Default")
      (node (ref "CARD1") (pin "19") (pinfunction "3_19") (pintype "passive"))
    )
    (net (code "77") (name "unconnected-(CARD1B-4-Pad20)") (class "Default")
      (node (ref "CARD1") (pin "20") (pinfunction "4_20") (pintype "passive"))
    )
    (net (code "78") (name "unconnected-(CARD1B-5-Pad21)") (class "Default")
      (node (ref "CARD1") (pin "21") (pinfunction "5_21") (pintype "passive"))
    )
    (net (code "79") (name "unconnected-(CARD1B-6-Pad22)") (class "Default")
      (node (ref "CARD1") (pin "22") (pinfunction "6_22") (pintype "passive"))
    )
    (net (code "80") (name "unconnected-(CARD1B-7-Pad23)") (class "Default")
      (node (ref "CARD1") (pin "23") (pinfunction "7_23") (pintype "passive"))
    )
    (net (code "81") (name "unconnected-(CARD1B-8-Pad24)") (class "Default")
      (node (ref "CARD1") (pin "24") (pinfunction "8_24") (pintype "passive"))
    )
    (net (code "82") (name "unconnected-(CARD1B-10-Pad26)") (class "Default")
      (node (ref "CARD1") (pin "26") (pinfunction "10_26") (pintype "passive"))
    )
    (net (code "83") (name "unconnected-(CARD1B-12-Pad28)") (class "Default")
      (node (ref "CARD1") (pin "28") (pinfunction "12_28") (pintype "passive"))
    )
    (net (code "84") (name "unconnected-(CARD1B-14-Pad30)") (class "Default")
      (node (ref "CARD1") (pin "30") (pinfunction "14_30") (pintype "passive"))
    )
    (net (code "85") (name "unconnected-(U2-RA2-Pad21)") (class "Default")
      (node (ref "U2") (pin "21") (pinfunction "RA2_21") (pintype "bidirectional"))
    )
    (net (code "86") (name "unconnected-(U2-RA4-Pad23)") (class "Default")
      (node (ref "U2") (pin "23") (pinfunction "RA4_23") (pintype "bidirectional"))
    )
    (net (code "87") (name "unconnected-(U2-RA5-Pad24)") (class "Default")
      (node (ref "U2") (pin "24") (pinfunction "RA5_24") (pintype "bidirectional"))
    )
    (net (code "88") (name "unconnected-(U2-RA6-Pad31)") (class "Default")
      (node (ref "U2") (pin "31") (pinfunction "RA6_31") (pintype "bidirectional"))
    )
    (net (code "89") (name "unconnected-(U2-RA7-Pad30)") (class "Default")
      (node (ref "U2") (pin "30") (pinfunction "RA7_30") (pintype "bidirectional"))
    )
    (net (code "90") (name "unconnected-(U2-RB0-Pad8)") (class "Default")
      (node (ref "U2") (pin "8") (pinfunction "RB0_8") (pintype "bidirectional"))
    )
    (net (code "91") (name "unconnected-(U2-RB2-Pad10)") (class "Default")
      (node (ref "U2") (pin "10") (pinfunction "RB2_10") (pintype "bidirectional"))
    )
    (net (code "92") (name "unconnected-(U2-RB5-Pad15)") (class "Default")
      (node (ref "U2") (pin "15") (pinfunction "RB5_15") (pintype "bidirectional"))
    )
    (net (code "93") (name "unconnected-(U2-RC0-Pad32)") (class "Default")
      (node (ref "U2") (pin "32") (pinfunction "RC0_32") (pintype "bidirectional"))
    )
    (net (code "94") (name "unconnected-(U2-RC1-Pad35)") (class "Default")
      (node (ref "U2") (pin "35") (pinfunction "RC1_35") (pintype "bidirectional"))
    )
    (net (code "95") (name "unconnected-(U2-RC2-Pad36)") (class "Default")
      (node (ref "U2") (pin "36") (pinfunction "RC2_36") (pintype "bidirectional"))
    )
    (net (code "96") (name "unconnected-(U2-RC3-Pad37)") (class "Default")
      (node (ref "U2") (pin "37") (pinfunction "RC3_37") (pintype "bidirectional"))
    )
    (net (code "97") (name "unconnected-(U2-RC4-Pad42)") (class "Default")
      (node (ref "U2") (pin "42") (pinfunction "RC4_42") (pintype "bidirectional"))
    )
    (net (code "98") (name "unconnected-(U2-RD0-Pad38)") (class "Default")
      (node (ref "U2") (pin "38") (pinfunction "RD0_38") (pintype "bidirectional"))
    )
    (net (code "99") (name "unconnected-(U2-RD1-Pad39)") (class "Default")
      (node (ref "U2") (pin "39") (pinfunction "RD1_39") (pintype "bidirectional"))
    )
    (net (code "100") (name "unconnected-(U2-RD2-Pad40)") (class "Default")
      (node (ref "U2") (pin "40") (pinfunction "RD2_40") (pintype "bidirectional"))
    )
    (net (code "101") (name "unconnected-(U2-RD3-Pad41)") (class "Default")
      (node (ref "U2") (pin "41") (pinfunction "RD3_41") (pintype "bidirectional"))
    )
    (net (code "102") (name "unconnected-(U2-RD4-Pad2)") (class "Default")
      (node (ref "U2") (pin "2") (pinfunction "RD4_2") (pintype "bidirectional"))
    )
    (net (code "103") (name "unconnected-(U2-RE0-Pad25)") (class "Default")
      (node (ref "U2") (pin "25") (pinfunction "RE0_25") (pintype "bidirectional"))
    )
    (net (code "104") (name "unconnected-(U2-RE1-Pad26)") (class "Default")
      (node (ref "U2") (pin "26") (pinfunction "RE1_26") (pintype "bidirectional"))
    )
    (net (code "105") (name "unconnected-(U2-RE2-Pad27)") (class "Default")
      (node (ref "U2") (pin "27") (pinfunction "RE2_27") (pintype "bidirectional"))
    )
  )
)
